# ACE.net
KiCad netlist of a schematic drawn in EAGLE
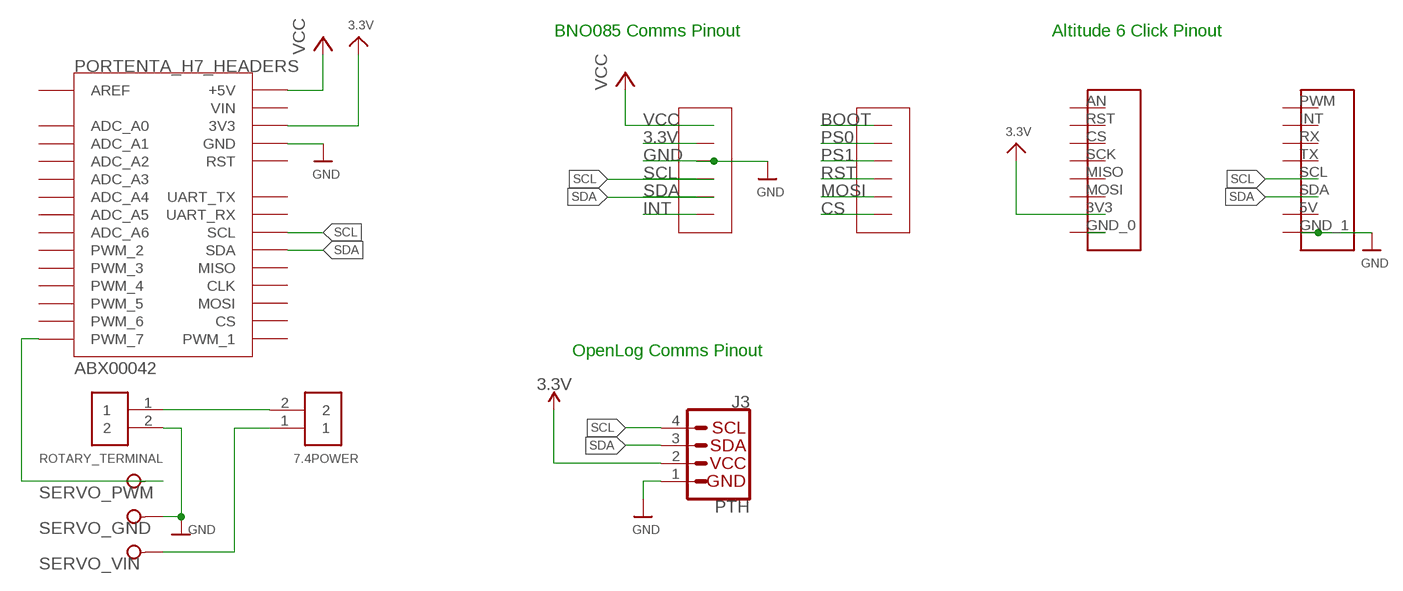
[diagram p0: schematic, sheet 1]

(export (version "E")
  (design (tool "Eeschema 10.0.6"))
  (components
    (comp (ref "7.4POWER")
      (value "282837-2")
      (footprint "eagle-import:TE_282837-2")
      (fields (field (name "MF") "TE Connectivity"))
      (libsource (lib "eagle-import") (part "282837-2"))
    )
    (comp (ref "J3")
      (value "PTH")
      (footprint "eagle-import:1X04_NO_SILK")
      (libsource (lib "eagle-import") (part "I2C_STANDARD_NO_SILK"))
    )
    (comp (ref "ROTARY_TERMINAL")
      (value "282837-2")
      (footprint "eagle-import:TE_282837-2")
      (fields (field (name "MF") "TE Connectivity"))
      (libsource (lib "eagle-import") (part "282837-2"))
    )
    (comp (ref "SERVO")
      (value "W237-3E")
      (footprint "eagle-import:W237-3E")
      (libsource (lib "eagle-import") (part "W237-3E"))
    )
    (comp (ref "U$1")
      (value "MIKROE-ALTITUDE-6-CLICK-DVC")
      (footprint "eagle-import:MIKROE-ALTITUDE-6-CLICK-PINOUT")
      (libsource (lib "eagle-import") (part "MIKROE-ALTITUDE-6-CLICK-DVC"))
    )
    (comp (ref "U$5")
      (value "ADAFRUIT_BNO08X")
      (footprint "eagle-import:ADAFRUIT_BNO08X_FOOTPRINT")
      (libsource (lib "eagle-import") (part "ADAFRUIT_BNO08X"))
    )
    (comp (ref "U$10")
      (value "ABX00042_HEADERS_IO")
      (footprint "eagle-import:MODULE_ABX00042_HEADERS")
      (libsource (lib "eagle-import") (part "ABX00042_HEADERS_IO"))
    )
  )
  (nets
    (net (code "1") (name "/SERVO_GND") (class "Default")
      (node (ref "7.4POWER") (pin "2") (pinfunction "2_2") (pintype "passive"))
      (node (ref "ROTARY_TERMINAL") (pin "1") (pinfunction "1_1") (pintype "passive"))
    )
    (net (code "2") (name "/SERVO_PWM") (class "Default")
      (node (ref "SERVO") (pin "1") (pinfunction "KL_1") (pintype "passive"))
      (node (ref "U$10") (pin "J9") (pinfunction "PWM_7_J9") (pintype "bidirectional"))
    )
    (net (code "3") (name "/SERVO_VIN") (class "Default")
      (node (ref "7.4POWER") (pin "1") (pinfunction "1_1") (pintype "passive"))
      (node (ref "SERVO") (pin "3") (pinfunction "KL_3") (pintype "passive"))
    )
    (net (code "4") (name "3.3V") (class "Default")
      (node (ref "J3") (pin "2") (pinfunction "VCC_2") (pintype "power_in"))
      (node (ref "U$1") (pin "3V3") (pinfunction "3.3V_3V3") (pintype "bidirectional"))
      (node (ref "U$10") (pin "J17") (pinfunction "3V3_J17") (pintype "bidirectional"))
    )
    (net (code "5") (name "GND") (class "Default")
      (node (ref "J3") (pin "1") (pinfunction "GND_1") (pintype "power_in"))
      (node (ref "ROTARY_TERMINAL") (pin "2") (pinfunction "2_2") (pintype "passive"))
      (node (ref "SERVO") (pin "2") (pinfunction "KL_2") (pintype "passive"))
      (node (ref "U$1") (pin "GND_1") (pinfunction "GND_1_GND_1") (pintype "bidirectional"))
      (node (ref "U$10") (pin "J18") (pinfunction "GND_J18") (pintype "bidirectional"))
      (node (ref "U$5") (pin "GND") (pinfunction "GND_GND") (pintype "bidirectional"))
    )
    (net (code "6") (name "SCL") (class "Default")
      (node (ref "J3") (pin "4") (pinfunction "SCL_4") (pintype "passive"))
      (node (ref "U$1") (pin "SCL") (pinfunction "SCL_SCL") (pintype "bidirectional"))
      (node (ref "U$10") (pin "J22") (pinfunction "SCL_J22") (pintype "bidirectional"))
      (node (ref "U$5") (pin "SCL") (pinfunction "SCL_SCL") (pintype "bidirectional"))
    )
    (net (code "7") (name "SDA") (class "Default")
      (node (ref "J3") (pin "3") (pinfunction "SDA_3") (pintype "passive"))
      (node (ref "U$1") (pin "SDA") (pinfunction "SDA_SDA") (pintype "bidirectional"))
      (node (ref "U$10") (pin "J23") (pinfunction "SDA_J23") (pintype "bidirectional"))
      (node (ref "U$5") (pin "SDA") (pinfunction "SDA_SDA") (pintype "bidirectional"))
    )
    (net (code "8") (name "VCC") (class "Default")
      (node (ref "U$10") (pin "J15") (pinfunction "+5V_J15") (pintype "bidirectional"))
      (node (ref "U$5") (pin "VIN") (pinfunction "VCC_VIN") (pintype "bidirectional"))
    )
    (net (code "9") (name "unconnected-(U$1-Pad5V)") (class "Default")
      (node (ref "U$1") (pin "5V") (pinfunction "5V_5V") (pintype "bidirectional"))
    )
    (net (code "10") (name "unconnected-(U$1-PadAN)") (class "Default")
      (node (ref "U$1") (pin "AN") (pinfunction "AN_AN") (pintype "bidirectional"))
    )
    (net (code "11") (name "unconnected-(U$1-PadCS)") (class "Default")
      (node (ref "U$1") (pin "CS") (pinfunction "CS_CS") (pintype "bidirectional"))
    )
    (net (code "12") (name "unconnected-(U$1-PadGND_0)") (class "Default")
      (node (ref "U$1") (pin "GND_0") (pinfunction "GND_0_GND_0") (pintype "bidirectional"))
    )
    (net (code "13") (name "unconnected-(U$1-PadINT)") (class "Default")
      (node (ref "U$1") (pin "INT") (pinfunction "INT_INT") (pintype "bidirectional"))
    )
    (net (code "14") (name "unconnected-(U$1-PadMISO)") (class "Default")
      (node (ref "U$1") (pin "MISO") (pinfunction "MISO_MISO") (pintype "bidirectional"))
    )
    (net (code "15") (name "unconnected-(U$1-PadMOSI)") (class "Default")
      (node (ref "U$1") (pin "MOSI") (pinfunction "MOSI_MOSI") (pintype "bidirectional"))
    )
    (net (code "16") (name "unconnected-(U$1-PadPWM)") (class "Default")
      (node (ref "U$1") (pin "PWM") (pinfunction "PWM_PWM") (pintype "bidirectional"))
    )
    (net (code "17") (name "unconnected-(U$1-PadRST)") (class "Default")
      (node (ref "U$1") (pin "RST") (pinfunction "RST_RST") (pintype "bidirectional"))
    )
    (net (code "18") (name "unconnected-(U$1-PadRX)") (class "Default")
      (node (ref "U$1") (pin "RX") (pinfunction "RX_RX") (pintype "bidirectional"))
    )
    (net (code "19") (name "unconnected-(U$1-PadSCK)") (class "Default")
      (node (ref "U$1") (pin "SCK") (pinfunction "SCK_SCK") (pintype "bidirectional"))
    )
    (net (code "20") (name "unconnected-(U$1-PadTX)") (class "Default")
      (node (ref "U$1") (pin "TX") (pinfunction "TX_TX") (pintype "bidirectional"))
    )
    (net (code "21") (name "unconnected-(U$5-3.3V-Pad3VO)") (class "Default")
      (node (ref "U$5") (pin "3VO") (pinfunction "3.3V_3VO") (pintype "bidirectional"))
    )
    (net (code "22") (name "unconnected-(U$5-BOOT-PadBT)") (class "Default")
      (node (ref "U$5") (pin "BT") (pinfunction "BOOT_BT") (pintype "bidirectional"))
    )
    (net (code "23") (name "unconnected-(U$5-MOSI-PadDI)") (class "Default")
      (node (ref "U$5") (pin "DI") (pinfunction "MOSI_DI") (pintype "bidirectional"))
    )
    (net (code "24") (name "unconnected-(U$5-PS0-PadP0)") (class "Default")
      (node (ref "U$5") (pin "P0") (pinfunction "PS0_P0") (pintype "bidirectional"))
    )
    (net (code "25") (name "unconnected-(U$5-PS1-PadP1)") (class "Default")
      (node (ref "U$5") (pin "P1") (pinfunction "PS1_P1") (pintype "bidirectional"))
    )
    (net (code "26") (name "unconnected-(U$5-PadCS)") (class "Default")
      (node (ref "U$5") (pin "CS") (pinfunction "CS_CS") (pintype "bidirectional"))
    )
    (net (code "27") (name "unconnected-(U$5-PadINT)") (class "Default")
      (node (ref "U$5") (pin "INT") (pinfunction "INT_INT") (pintype "bidirectional"))
    )
    (net (code "28") (name "unconnected-(U$5-PadRST)") (class "Default")
      (node (ref "U$5") (pin "RST") (pinfunction "RST_RST") (pintype "bidirectional"))
    )
    (net (code "29") (name "unconnected-(U$10-ADC_A0-PadJ2)") (class "Default")
      (node (ref "U$10") (pin "J2") (pinfunction "ADC_A0_J2") (pintype "bidirectional"))
    )
    (net (code "30") (name "unconnected-(U$10-ADC_A1-PadJ3)") (class "Default")
      (node (ref "U$10") (pin "J3") (pinfunction "ADC_A1_J3") (pintype "bidirectional"))
    )
    (net (code "31") (name "unconnected-(U$10-ADC_A2-PadJ4)") (class "Default")
      (node (ref "U$10") (pin "J4") (pinfunction "ADC_A2_J4") (pintype "bidirectional"))
    )
    (net (code "32") (name "unconnected-(U$10-ADC_A3-PadJ5)") (class "Default")
      (node (ref "U$10") (pin "J5") (pinfunction "ADC_A3_J5") (pintype "bidirectional"))
    )
    (net (code "33") (name "unconnected-(U$10-ADC_A4-PadJ6)") (class "Default")
      (node (ref "U$10") (pin "J6") (pinfunction "ADC_A4_J6") (pintype "bidirectional"))
    )
    (net (code "34") (name "unconnected-(U$10-ADC_A5-PadJ7)") (class "Default")
      (node (ref "U$10") (pin "J7") (pinfunction "ADC_A5_J7") (pintype "bidirectional"))
    )
    (net (code "35") (name "unconnected-(U$10-ADC_A6-PadJ8)") (class "Default")
      (node (ref "U$10") (pin "J8") (pinfunction "ADC_A6_J8") (pintype "bidirectional"))
    )
    (net (code "36") (name "unconnected-(U$10-AREF-PadJ1)") (class "Default")
      (node (ref "U$10") (pin "J1") (pinfunction "AREF_J1") (pintype "bidirectional"))
    )
    (net (code "37") (name "unconnected-(U$10-CLK-PadJ25)") (class "Default")
      (node (ref "U$10") (pin "J25") (pinfunction "CLK_J25") (pintype "bidirectional"))
    )
    (net (code "38") (name "unconnected-(U$10-CS-PadJ27)") (class "Default")
      (node (ref "U$10") (pin "J27") (pinfunction "CS_J27") (pintype "bidirectional"))
    )
    (net (code "39") (name "unconnected-(U$10-MISO-PadJ24)") (class "Default")
      (node (ref "U$10") (pin "J24") (pinfunction "MISO_J24") (pintype "bidirectional"))
    )
    (net (code "40") (name "unconnected-(U$10-MOSI-PadJ26)") (class "Default")
      (node (ref "U$10") (pin "J26") (pinfunction "MOSI_J26") (pintype "bidirectional"))
    )
    (net (code "41") (name "unconnected-(U$10-PWM_1-PadJ28)") (class "Default")
      (node (ref "U$10") (pin "J28") (pinfunction "PWM_1_J28") (pintype "bidirectional"))
    )
    (net (code "42") (name "unconnected-(U$10-PWM_2-PadJ14)") (class "Default")
      (node (ref "U$10") (pin "J14") (pinfunction "PWM_2_J14") (pintype "bidirectional"))
    )
    (net (code "43") (name "unconnected-(U$10-PWM_3-PadJ13)") (class "Default")
      (node (ref "U$10") (pin "J13") (pinfunction "PWM_3_J13") (pintype "bidirectional"))
    )
    (net (code "44") (name "unconnected-(U$10-PWM_4-PadJ12)") (class "Default")
      (node (ref "U$10") (pin "J12") (pinfunction "PWM_4_J12") (pintype "bidirectional"))
    )
    (net (code "45") (name "unconnected-(U$10-PWM_5-PadJ11)") (class "Default")
      (node (ref "U$10") (pin "J11") (pinfunction "PWM_5_J11") (pintype "bidirectional"))
    )
    (net (code "46") (name "unconnected-(U$10-PWM_6-PadJ10)") (class "Default")
      (node (ref "U$10") (pin "J10") (pinfunction "PWM_6_J10") (pintype "bidirectional"))
    )
    (net (code "47") (name "unconnected-(U$10-RST-PadJ19)") (class "Default")
      (node (ref "U$10") (pin "J19") (pinfunction "RST_J19") (pintype "bidirectional"))
    )
    (net (code "48") (name "unconnected-(U$10-UART_RX-PadJ21)") (class "Default")
      (node (ref "U$10") (pin "J21") (pinfunction "UART_RX_J21") (pintype "bidirectional"))
    )
    (net (code "49") (name "unconnected-(U$10-UART_TX-PadJ20)") (class "Default")
      (node (ref "U$10") (pin "J20") (pinfunction "UART_TX_J20") (pintype "bidirectional"))
    )
    (net (code "50") (name "unconnected-(U$10-VIN-PadJ16)") (class "Default")
      (node (ref "U$10") (pin "J16") (pinfunction "VIN_J16") (pintype "bidirectional"))
    )
  )
)
